# Sheet1_BUS_DATN.net
KiCad netlist of a schematic drawn in Altium Designer
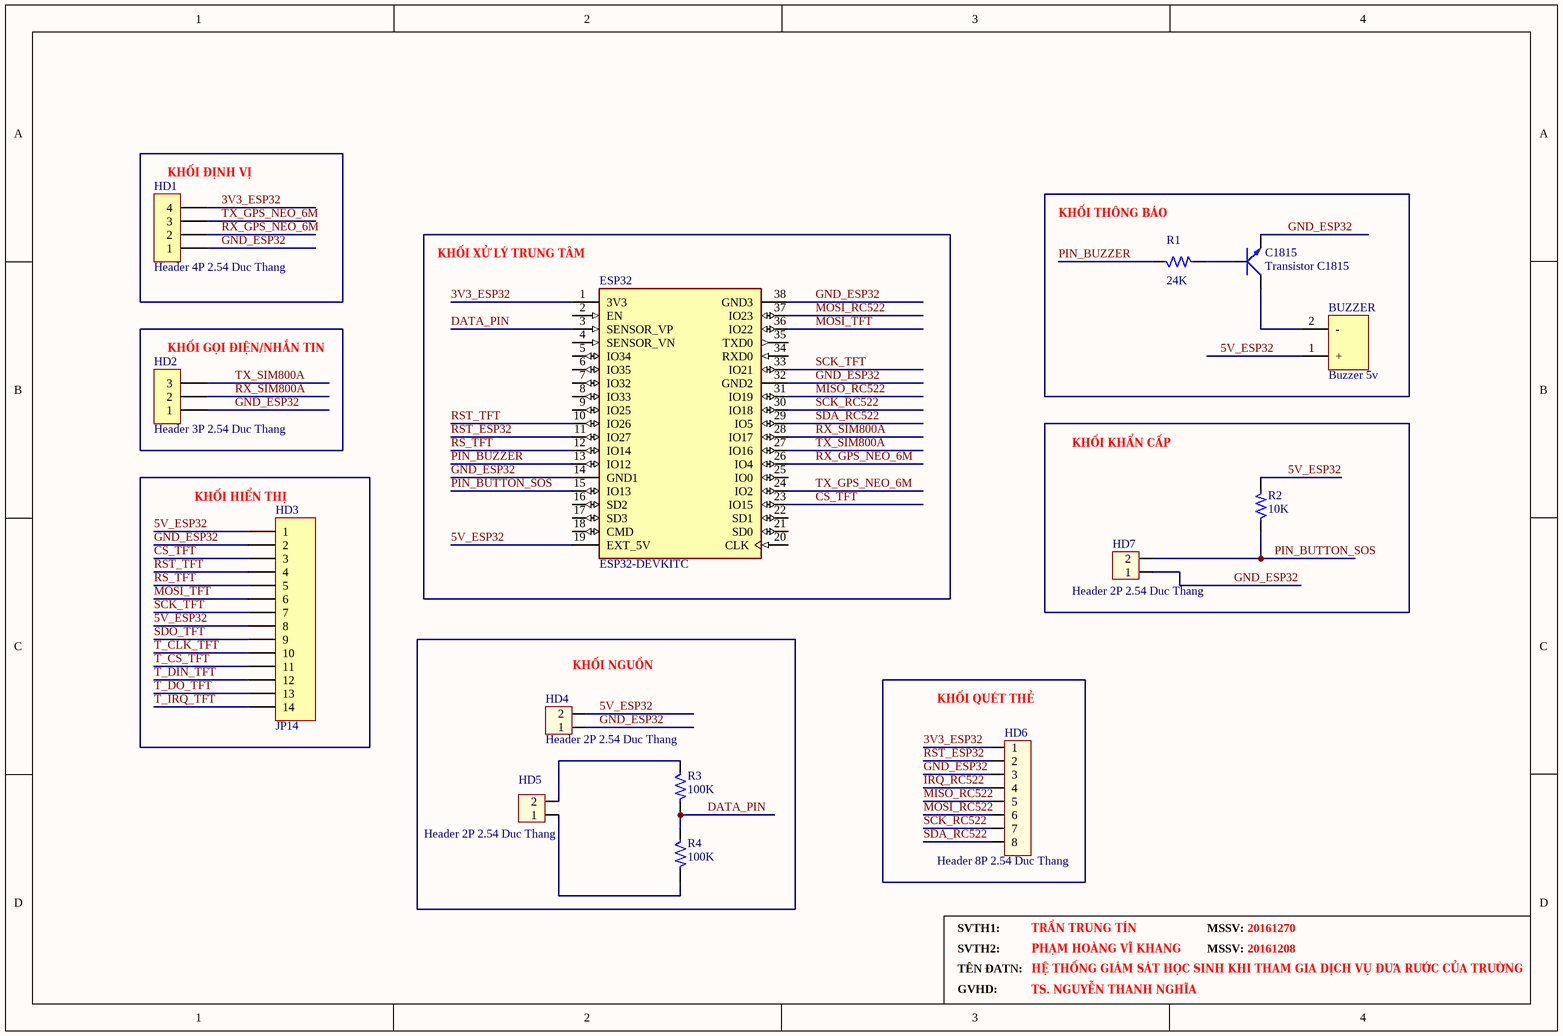
[diagram p0: Sheet1_BUS_DATN.SchDoc]

(export (version "E")
  (design (tool "Eeschema 10.0.6"))
  (components
    (comp (ref "BUZZER")
      (value "Buzzer 5v")
      (footprint "Buzzer 5v")
      (libsource (lib "Stm32") (part "Buzzer 5v"))
    )
    (comp (ref "C1815")
      (value "Transistor C1815")
      (footprint "TO126")
      (description "NPN 600mW, ECB")
      (libsource (lib "Devzone_SCHLib") (part "C1815"))
    )
    (comp (ref "ESP32")
      (value "ESP32-DEVKITC")
      (footprint "MODULE_ESP32-DEVKITC")
      (fields (field (name "MP") "ESP32-DEVKITC-32D-F") (field (name "MF") "Espressif Systems"))
      (libsource (lib "SnapEDAsch") (part "ESP32-DEVKITC"))
    )
    (comp (ref "HD1")
      (value "Header 4P 2.54 Duc Thang")
      (footprint "XH2.54M-4")
      (description "Cắm")
      (libsource (lib "Header") (part "Header 4P 2.54 Duc Thang"))
    )
    (comp (ref "HD2")
      (value "Header 3P 2.54 Duc Thang")
      (footprint "XH2.54M-3")
      (description "Cắm")
      (libsource (lib "Header") (part "Header 3P 2.54 Duc Thang"))
    )
    (comp (ref "HD3")
      (value "JP14")
      (footprint "JP14-C1T")
      (description "WR-PHD 2.54 mm Angled Socket Header")
      (fields
        (field (name "MANUFACTURER") "Würth Elektronik eiSos GmbH")
        (field (name "PARTNO") "613014143121")
        (field (name "CREATED BY") "Karrer Zheng")
      )
      (libsource (lib "My Library") (part "JP14"))
    )
    (comp (ref "HD4")
      (value "Header 2P 2.54 Duc Thang")
      (footprint "XH2.54M-2")
      (description "Cắm")
      (libsource (lib "Header") (part "Header 2P 2.54 Duc Thang"))
    )
    (comp (ref "HD5")
      (value "Header 2P 2.54 Duc Thang")
      (footprint "XH2.54M-2")
      (description "Cắm")
      (libsource (lib "Header") (part "Header 2P 2.54 Duc Thang"))
    )
    (comp (ref "HD6")
      (value "Header 8P 2.54 Duc Thang")
      (footprint "XH2.54M-8")
      (description "Cắm")
      (libsource (lib "Header") (part "Header 8P 2.54 Duc Thang"))
    )
    (comp (ref "HD7")
      (value "Header 2P 2.54 Duc Thang")
      (footprint "XH2.54M-2")
      (description "Cắm")
      (libsource (lib "Header") (part "Header 2P 2.54 Duc Thang"))
    )
    (comp (ref "R1")
      (value "24K")
      (footprint "R1/4W")
      (description "Resistor 1/4W")
      (libsource (lib "syhaunguyen") (part "R"))
    )
    (comp (ref "R2")
      (value "10K")
      (footprint "R1/4W")
      (description "Resistor 1/4W")
      (libsource (lib "syhaunguyen") (part "R"))
    )
    (comp (ref "R3")
      (value "100K")
      (footprint "R1/4W")
      (description "Resistor 1/4W")
      (libsource (lib "syhaunguyen") (part "R"))
    )
    (comp (ref "R4")
      (value "100K")
      (footprint "R1/4W")
      (description "Resistor 1/4W")
      (libsource (lib "syhaunguyen") (part "R"))
    )
  )
  (nets
    (net (code "1") (name "/3V3_ESP32") (class "Default")
      (node (ref "ESP32") (pin "1") (pinfunction "3V3_1") (pintype "power_in"))
      (node (ref "HD1") (pin "4") (pinfunction "4_4") (pintype "passive"))
      (node (ref "HD6") (pin "1") (pinfunction "1_1") (pintype "passive"))
    )
    (net (code "2") (name "/5V_ESP32") (class "Default")
      (node (ref "BUZZER") (pin "1") (pinfunction "+_1") (pintype "passive"))
      (node (ref "ESP32") (pin "19") (pinfunction "EXT_5V_19") (pintype "power_in"))
      (node (ref "HD3") (pin "1") (pinfunction "1_1") (pintype "passive"))
      (node (ref "HD3") (pin "8") (pinfunction "8_8") (pintype "passive"))
      (node (ref "HD4") (pin "2") (pinfunction "2_2") (pintype "passive"))
      (node (ref "R2") (pin "2") (pinfunction "2_2") (pintype "passive"))
    )
    (net (code "3") (name "/CS_TFT") (class "Default")
      (node (ref "ESP32") (pin "23") (pinfunction "IO15_23") (pintype "bidirectional"))
      (node (ref "HD3") (pin "3") (pinfunction "3_3") (pintype "passive"))
    )
    (net (code "4") (name "/DATA_PIN") (class "Default")
      (node (ref "ESP32") (pin "3") (pinfunction "SENSOR_VP_3") (pintype "input"))
      (node (ref "R3") (pin "2") (pinfunction "2_2") (pintype "passive"))
      (node (ref "R4") (pin "1") (pinfunction "1_1") (pintype "passive"))
    )
    (net (code "5") (name "/GND_ESP32") (class "Default")
      (node (ref "C1815") (pin "3") (pinfunction "E_3") (pintype "passive"))
      (node (ref "ESP32") (pin "14") (pinfunction "GND1_14") (pintype "power_in"))
      (node (ref "ESP32") (pin "32") (pinfunction "GND2_32") (pintype "power_in"))
      (node (ref "ESP32") (pin "38") (pinfunction "GND3_38") (pintype "power_in"))
      (node (ref "HD1") (pin "1") (pinfunction "1_1") (pintype "passive"))
      (node (ref "HD2") (pin "1") (pinfunction "1_1") (pintype "passive"))
      (node (ref "HD3") (pin "2") (pinfunction "2_2") (pintype "passive"))
      (node (ref "HD4") (pin "1") (pinfunction "1_1") (pintype "passive"))
      (node (ref "HD6") (pin "3") (pinfunction "3_3") (pintype "passive"))
      (node (ref "HD7") (pin "1") (pinfunction "1_1") (pintype "passive"))
    )
    (net (code "6") (name "/IRQ_RC522") (class "Default")
      (node (ref "HD6") (pin "4") (pinfunction "4_4") (pintype "passive"))
    )
    (net (code "7") (name "/MISO_RC522") (class "Default")
      (node (ref "ESP32") (pin "31") (pinfunction "IO19_31") (pintype "bidirectional"))
      (node (ref "HD6") (pin "5") (pinfunction "5_5") (pintype "passive"))
    )
    (net (code "8") (name "/MOSI_RC522") (class "Default")
      (node (ref "ESP32") (pin "37") (pinfunction "IO23_37") (pintype "bidirectional"))
      (node (ref "HD6") (pin "6") (pinfunction "6_6") (pintype "passive"))
    )
    (net (code "9") (name "/MOSI_TFT") (class "Default")
      (node (ref "ESP32") (pin "36") (pinfunction "IO22_36") (pintype "bidirectional"))
      (node (ref "HD3") (pin "6") (pinfunction "6_6") (pintype "passive"))
    )
    (net (code "10") (name "/PIN_BUTTON_SOS") (class "Default")
      (node (ref "ESP32") (pin "15") (pinfunction "IO13_15") (pintype "bidirectional"))
      (node (ref "HD7") (pin "2") (pinfunction "2_2") (pintype "passive"))
      (node (ref "R2") (pin "1") (pinfunction "1_1") (pintype "passive"))
    )
    (net (code "11") (name "/PIN_BUZZER") (class "Default")
      (node (ref "ESP32") (pin "13") (pinfunction "IO12_13") (pintype "bidirectional"))
      (node (ref "R1") (pin "1") (pinfunction "1_1") (pintype "passive"))
    )
    (net (code "12") (name "/RST_ESP32") (class "Default")
      (node (ref "ESP32") (pin "11") (pinfunction "IO27_11") (pintype "bidirectional"))
      (node (ref "HD6") (pin "2") (pinfunction "2_2") (pintype "passive"))
    )
    (net (code "13") (name "/RST_TFT") (class "Default")
      (node (ref "ESP32") (pin "10") (pinfunction "IO26_10") (pintype "bidirectional"))
      (node (ref "HD3") (pin "4") (pinfunction "4_4") (pintype "passive"))
    )
    (net (code "14") (name "/RS_TFT") (class "Default")
      (node (ref "ESP32") (pin "12") (pinfunction "IO14_12") (pintype "bidirectional"))
      (node (ref "HD3") (pin "5") (pinfunction "5_5") (pintype "passive"))
    )
    (net (code "15") (name "/RX_GPS_NEO_6M") (class "Default")
      (node (ref "ESP32") (pin "26") (pinfunction "IO4_26") (pintype "bidirectional"))
      (node (ref "HD1") (pin "2") (pinfunction "2_2") (pintype "passive"))
    )
    (net (code "16") (name "/RX_SIM800A") (class "Default")
      (node (ref "ESP32") (pin "28") (pinfunction "IO17_28") (pintype "bidirectional"))
      (node (ref "HD2") (pin "2") (pinfunction "2_2") (pintype "passive"))
    )
    (net (code "17") (name "/SCK_RC522") (class "Default")
      (node (ref "ESP32") (pin "30") (pinfunction "IO18_30") (pintype "bidirectional"))
      (node (ref "HD6") (pin "7") (pinfunction "7_7") (pintype "passive"))
    )
    (net (code "18") (name "/SCK_TFT") (class "Default")
      (node (ref "ESP32") (pin "33") (pinfunction "IO21_33") (pintype "bidirectional"))
      (node (ref "HD3") (pin "7") (pinfunction "7_7") (pintype "passive"))
    )
    (net (code "19") (name "/SDA_RC522") (class "Default")
      (node (ref "ESP32") (pin "29") (pinfunction "IO5_29") (pintype "bidirectional"))
      (node (ref "HD6") (pin "8") (pinfunction "8_8") (pintype "passive"))
    )
    (net (code "20") (name "/SDO_TFT") (class "Default")
      (node (ref "HD3") (pin "9") (pinfunction "9_9") (pintype "passive"))
    )
    (net (code "21") (name "/TX_GPS_NEO_6M") (class "Default")
      (node (ref "ESP32") (pin "24") (pinfunction "IO2_24") (pintype "bidirectional"))
      (node (ref "HD1") (pin "3") (pinfunction "3_3") (pintype "passive"))
    )
    (net (code "22") (name "/TX_SIM800A") (class "Default")
      (node (ref "ESP32") (pin "27") (pinfunction "IO16_27") (pintype "bidirectional"))
      (node (ref "HD2") (pin "3") (pinfunction "3_3") (pintype "passive"))
    )
    (net (code "23") (name "/T_CLK_TFT") (class "Default")
      (node (ref "HD3") (pin "10") (pinfunction "10_10") (pintype "passive"))
    )
    (net (code "24") (name "/T_CS_TFT") (class "Default")
      (node (ref "HD3") (pin "11") (pinfunction "11_11") (pintype "passive"))
    )
    (net (code "25") (name "/T_DIN_TFT") (class "Default")
      (node (ref "HD3") (pin "12") (pinfunction "12_12") (pintype "passive"))
    )
    (net (code "26") (name "/T_DO_TFT") (class "Default")
      (node (ref "HD3") (pin "13") (pinfunction "13_13") (pintype "passive"))
    )
    (net (code "27") (name "/T_IRQ_TFT") (class "Default")
      (node (ref "HD3") (pin "14") (pinfunction "14_14") (pintype "passive"))
    )
    (net (code "28") (name "Net-(BUZZER--)") (class "Default")
      (node (ref "BUZZER") (pin "2") (pinfunction "-_2") (pintype "passive"))
      (node (ref "C1815") (pin "2") (pinfunction "C_2") (pintype "passive"))
    )
    (net (code "29") (name "Net-(C1815-B)") (class "Default")
      (node (ref "C1815") (pin "1") (pinfunction "B_1") (pintype "passive"))
      (node (ref "R1") (pin "2") (pinfunction "2_2") (pintype "passive"))
    )
    (net (code "30") (name "Net-(HD5-Pad1)") (class "Default")
      (node (ref "HD5") (pin "1") (pinfunction "1_1") (pintype "passive"))
      (node (ref "R4") (pin "2") (pinfunction "2_2") (pintype "passive"))
    )
    (net (code "31") (name "Net-(HD5-Pad2)") (class "Default")
      (node (ref "HD5") (pin "2") (pinfunction "2_2") (pintype "passive"))
      (node (ref "R3") (pin "1") (pinfunction "1_1") (pintype "passive"))
    )
    (net (code "32") (name "unconnected-(ESP32-CLK-Pad20)") (class "Default")
      (node (ref "ESP32") (pin "20") (pinfunction "CLK_20") (pintype "input"))
    )
    (net (code "33") (name "unconnected-(ESP32-CMD-Pad18)") (class "Default")
      (node (ref "ESP32") (pin "18") (pinfunction "CMD_18") (pintype "bidirectional"))
    )
    (net (code "34") (name "unconnected-(ESP32-EN-Pad2)") (class "Default")
      (node (ref "ESP32") (pin "2") (pinfunction "EN_2") (pintype "input"))
    )
    (net (code "35") (name "unconnected-(ESP32-IO0-Pad25)") (class "Default")
      (node (ref "ESP32") (pin "25") (pinfunction "IO0_25") (pintype "bidirectional"))
    )
    (net (code "36") (name "unconnected-(ESP32-IO25-Pad9)") (class "Default")
      (node (ref "ESP32") (pin "9") (pinfunction "IO25_9") (pintype "bidirectional"))
    )
    (net (code "37") (name "unconnected-(ESP32-IO32-Pad7)") (class "Default")
      (node (ref "ESP32") (pin "7") (pinfunction "IO32_7") (pintype "bidirectional"))
    )
    (net (code "38") (name "unconnected-(ESP32-IO33-Pad8)") (class "Default")
      (node (ref "ESP32") (pin "8") (pinfunction "IO33_8") (pintype "bidirectional"))
    )
    (net (code "39") (name "unconnected-(ESP32-IO34-Pad5)") (class "Default")
      (node (ref "ESP32") (pin "5") (pinfunction "IO34_5") (pintype "bidirectional"))
    )
    (net (code "40") (name "unconnected-(ESP32-IO35-Pad6)") (class "Default")
      (node (ref "ESP32") (pin "6") (pinfunction "IO35_6") (pintype "bidirectional"))
    )
    (net (code "41") (name "unconnected-(ESP32-RXD0-Pad34)") (class "Default")
      (node (ref "ESP32") (pin "34") (pinfunction "RXD0_34") (pintype "input"))
    )
    (net (code "42") (name "unconnected-(ESP32-SD0-Pad21)") (class "Default")
      (node (ref "ESP32") (pin "21") (pinfunction "SD0_21") (pintype "bidirectional"))
    )
    (net (code "43") (name "unconnected-(ESP32-SD1-Pad22)") (class "Default")
      (node (ref "ESP32") (pin "22") (pinfunction "SD1_22") (pintype "bidirectional"))
    )
    (net (code "44") (name "unconnected-(ESP32-SD2-Pad16)") (class "Default")
      (node (ref "ESP32") (pin "16") (pinfunction "SD2_16") (pintype "bidirectional"))
    )
    (net (code "45") (name "unconnected-(ESP32-SD3-Pad17)") (class "Default")
      (node (ref "ESP32") (pin "17") (pinfunction "SD3_17") (pintype "bidirectional"))
    )
    (net (code "46") (name "unconnected-(ESP32-SENSOR_VN-Pad4)") (class "Default")
      (node (ref "ESP32") (pin "4") (pinfunction "SENSOR_VN_4") (pintype "input"))
    )
    (net (code "47") (name "unconnected-(ESP32-TXD0-Pad35)") (class "Default")
      (node (ref "ESP32") (pin "35") (pinfunction "TXD0_35") (pintype "output"))
    )
  )
)
